# drivehersch.net
KiCad netlist of a schematic drawn in EAGLE
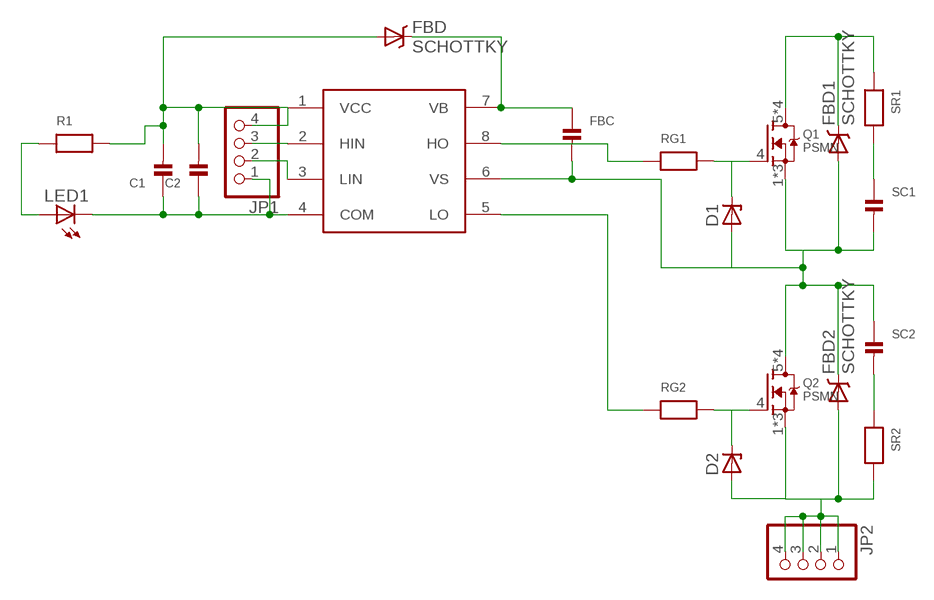
[diagram p0: schematic, sheet 1]

(export (version "E")
  (design (tool "Eeschema 10.0.6"))
  (components
    (comp (ref "C1")
      (value "CAP_CERAMIC1206")
      (footprint "eagle-import:1206")
      (libsource (lib "eagle-import") (part "CAP_CERAMIC1206"))
    )
    (comp (ref "C2")
      (value "CAP_CERAMIC1206")
      (footprint "eagle-import:1206")
      (libsource (lib "eagle-import") (part "CAP_CERAMIC1206"))
    )
    (comp (ref "D1")
      (value "ZENER-DIODESOT23")
      (footprint "eagle-import:SOT23")
      (libsource (lib "eagle-import") (part "ZENER-DIODESOT23"))
    )
    (comp (ref "D2")
      (value "ZENER-DIODESOT23")
      (footprint "eagle-import:SOT23")
      (libsource (lib "eagle-import") (part "ZENER-DIODESOT23"))
    )
    (comp (ref "FBC")
      (value "CAP_CERAMIC1206")
      (footprint "eagle-import:1206")
      (libsource (lib "eagle-import") (part "CAP_CERAMIC1206"))
    )
    (comp (ref "FBD")
      (value "SCHOTTKY")
      (footprint "eagle-import:SMA-DIODE")
      (libsource (lib "eagle-import") (part "SCHOTTKY"))
    )
    (comp (ref "FBD1")
      (value "SCHOTTKY")
      (footprint "eagle-import:SMA-DIODE")
      (libsource (lib "eagle-import") (part "SCHOTTKY"))
    )
    (comp (ref "FBD2")
      (value "SCHOTTKY")
      (footprint "eagle-import:SMA-DIODE")
      (libsource (lib "eagle-import") (part "SCHOTTKY"))
    )
    (comp (ref "JP1")
      (value "HEADER-1X4ROUND")
      (footprint "eagle-import:1X04_ROUND")
      (libsource (lib "eagle-import") (part "HEADER-1X4ROUND"))
    )
    (comp (ref "JP2")
      (value "HEADER-1X4ROUND")
      (footprint "eagle-import:1X04_ROUND")
      (libsource (lib "eagle-import") (part "HEADER-1X4ROUND"))
    )
    (comp (ref "LED1")
      (value "LEDCHIPLED_0603")
      (footprint "eagle-import:CHIPLED_0603")
      (libsource (lib "eagle-import") (part "LEDCHIPLED_0603"))
    )
    (comp (ref "Q1")
      (value "PSMN")
      (footprint "eagle-import:SO-08")
      (libsource (lib "eagle-import") (part "PSMN"))
    )
    (comp (ref "Q2")
      (value "PSMN")
      (footprint "eagle-import:SO-08")
      (libsource (lib "eagle-import") (part "PSMN"))
    )
    (comp (ref "R1")
      (value "RESISTOR0603")
      (footprint "eagle-import:0603")
      (libsource (lib "eagle-import") (part "RESISTOR0603"))
    )
    (comp (ref "RG1")
      (value "RESISTOR0603")
      (footprint "eagle-import:0603")
      (libsource (lib "eagle-import") (part "RESISTOR0603"))
    )
    (comp (ref "RG2")
      (value "RESISTOR0603")
      (footprint "eagle-import:0603")
      (libsource (lib "eagle-import") (part "RESISTOR0603"))
    )
    (comp (ref "SC1")
      (value "CAP_CERAMIC0603")
      (footprint "eagle-import:0603")
      (libsource (lib "eagle-import") (part "CAP_CERAMIC0603"))
    )
    (comp (ref "SC2")
      (value "CAP_CERAMIC0603")
      (footprint "eagle-import:0603")
      (libsource (lib "eagle-import") (part "CAP_CERAMIC0603"))
    )
    (comp (ref "SR1")
      (value "RESISTOR0603")
      (footprint "eagle-import:0603")
      (libsource (lib "eagle-import") (part "RESISTOR0603"))
    )
    (comp (ref "SR2")
      (value "RESISTOR0603")
      (footprint "eagle-import:0603")
      (libsource (lib "eagle-import") (part "RESISTOR0603"))
    )
    (comp (ref "U$1")
      (value "IRS218-67")
      (footprint "eagle-import:SO-08")
      (libsource (lib "eagle-import") (part "IRS218-67"))
    )
  )
  (nets
    (net (code "1") (name "/GND") (class "Default")
      (node (ref "C1") (pin "1") (pinfunction "P$1_1") (pintype "passive"))
      (node (ref "C2") (pin "1") (pinfunction "P$1_1") (pintype "passive"))
      (node (ref "D2") (pin "1") (pinfunction "A_1") (pintype "passive"))
      (node (ref "FBD2") (pin "A") (pinfunction "A_A") (pintype "passive"))
      (node (ref "JP1") (pin "1") (pinfunction "1_1") (pintype "passive"))
      (node (ref "JP2") (pin "1") (pinfunction "1_1") (pintype "passive"))
      (node (ref "JP2") (pin "2") (pinfunction "2_2") (pintype "passive"))
      (node (ref "JP2") (pin "3") (pinfunction "3_3") (pintype "passive"))
      (node (ref "JP2") (pin "4") (pinfunction "4_4") (pintype "passive"))
      (node (ref "LED1") (pin "C") (pinfunction "C_C") (pintype "passive"))
      (node (ref "Q2") (pin "1") (pinfunction "S_1") (pintype "bidirectional"))
      (node (ref "Q2") (pin "2") (pinfunction "S_2") (pintype "bidirectional"))
      (node (ref "Q2") (pin "3") (pinfunction "S_3") (pintype "bidirectional"))
      (node (ref "SR2") (pin "2") (pinfunction "2_2") (pintype "passive"))
      (node (ref "U$1") (pin "4") (pinfunction "COM_4") (pintype "bidirectional"))
    )
    (net (code "2") (name "Net-(C1-P$2)") (class "Default")
      (node (ref "C1") (pin "2") (pinfunction "P$2_2") (pintype "passive"))
      (node (ref "C2") (pin "2") (pinfunction "P$2_2") (pintype "passive"))
      (node (ref "FBD") (pin "A") (pinfunction "A_A") (pintype "passive"))
      (node (ref "JP1") (pin "4") (pinfunction "4_4") (pintype "passive"))
      (node (ref "R1") (pin "2") (pinfunction "2_2") (pintype "passive"))
      (node (ref "U$1") (pin "1") (pinfunction "VCC_1") (pintype "bidirectional"))
    )
    (net (code "3") (name "Net-(D1-A)") (class "Default")
      (node (ref "D1") (pin "1") (pinfunction "A_1") (pintype "passive"))
      (node (ref "FBC") (pin "2") (pinfunction "P$2_2") (pintype "passive"))
      (node (ref "FBD1") (pin "A") (pinfunction "A_A") (pintype "passive"))
      (node (ref "FBD2") (pin "C") (pinfunction "C_C") (pintype "passive"))
      (node (ref "Q1") (pin "1") (pinfunction "S_1") (pintype "bidirectional"))
      (node (ref "Q1") (pin "2") (pinfunction "S_2") (pintype "bidirectional"))
      (node (ref "Q1") (pin "3") (pinfunction "S_3") (pintype "bidirectional"))
      (node (ref "Q2") (pin "5") (pinfunction "D_5") (pintype "bidirectional"))
      (node (ref "Q2") (pin "6") (pinfunction "D_6") (pintype "bidirectional"))
      (node (ref "Q2") (pin "7") (pinfunction "D_7") (pintype "bidirectional"))
      (node (ref "Q2") (pin "8") (pinfunction "D_8") (pintype "bidirectional"))
      (node (ref "SC1") (pin "2") (pinfunction "P$2_2") (pintype "passive"))
      (node (ref "SC2") (pin "1") (pinfunction "P$1_1") (pintype "passive"))
      (node (ref "U$1") (pin "6") (pinfunction "VS_6") (pintype "bidirectional"))
    )
    (net (code "4") (name "Net-(D1-C)") (class "Default")
      (node (ref "D1") (pin "3") (pinfunction "C_3") (pintype "passive"))
      (node (ref "Q1") (pin "4") (pinfunction "G_4") (pintype "bidirectional"))
      (node (ref "RG1") (pin "2") (pinfunction "2_2") (pintype "passive"))
    )
    (net (code "5") (name "Net-(D2-C)") (class "Default")
      (node (ref "D2") (pin "3") (pinfunction "C_3") (pintype "passive"))
      (node (ref "Q2") (pin "4") (pinfunction "G_4") (pintype "bidirectional"))
      (node (ref "RG2") (pin "2") (pinfunction "2_2") (pintype "passive"))
    )
    (net (code "6") (name "Net-(FBC-P$1)") (class "Default")
      (node (ref "FBC") (pin "1") (pinfunction "P$1_1") (pintype "passive"))
      (node (ref "FBD") (pin "C") (pinfunction "C_C") (pintype "passive"))
      (node (ref "U$1") (pin "7") (pinfunction "VB_7") (pintype "bidirectional"))
    )
    (net (code "7") (name "Net-(FBD1-PadC)") (class "Default")
      (node (ref "FBD1") (pin "C") (pinfunction "C_C") (pintype "passive"))
      (node (ref "Q1") (pin "5") (pinfunction "D_5") (pintype "bidirectional"))
      (node (ref "Q1") (pin "6") (pinfunction "D_6") (pintype "bidirectional"))
      (node (ref "Q1") (pin "7") (pinfunction "D_7") (pintype "bidirectional"))
      (node (ref "Q1") (pin "8") (pinfunction "D_8") (pintype "bidirectional"))
      (node (ref "SR1") (pin "1") (pinfunction "1_1") (pintype "passive"))
    )
    (net (code "8") (name "Net-(LED1-PadA)") (class "Default")
      (node (ref "LED1") (pin "A") (pinfunction "A_A") (pintype "passive"))
      (node (ref "R1") (pin "1") (pinfunction "1_1") (pintype "passive"))
    )
    (net (code "9") (name "Net-(SC1-P$1)") (class "Default")
      (node (ref "SC1") (pin "1") (pinfunction "P$1_1") (pintype "passive"))
      (node (ref "SR1") (pin "2") (pinfunction "2_2") (pintype "passive"))
    )
    (net (code "10") (name "Net-(SC2-P$2)") (class "Default")
      (node (ref "SC2") (pin "2") (pinfunction "P$2_2") (pintype "passive"))
      (node (ref "SR2") (pin "1") (pinfunction "1_1") (pintype "passive"))
    )
    (net (code "11") (name "Net-(U$1-HIN)") (class "Default")
      (node (ref "JP1") (pin "3") (pinfunction "3_3") (pintype "passive"))
      (node (ref "U$1") (pin "2") (pinfunction "HIN_2") (pintype "bidirectional"))
    )
    (net (code "12") (name "Net-(U$1-HO)") (class "Default")
      (node (ref "RG1") (pin "1") (pinfunction "1_1") (pintype "passive"))
      (node (ref "U$1") (pin "8") (pinfunction "HO_8") (pintype "bidirectional"))
    )
    (net (code "13") (name "Net-(U$1-LIN)") (class "Default")
      (node (ref "JP1") (pin "2") (pinfunction "2_2") (pintype "passive"))
      (node (ref "U$1") (pin "3") (pinfunction "LIN_3") (pintype "bidirectional"))
    )
    (net (code "14") (name "Net-(U$1-LO)") (class "Default")
      (node (ref "RG2") (pin "1") (pinfunction "1_1") (pintype "passive"))
      (node (ref "U$1") (pin "5") (pinfunction "LO_5") (pintype "bidirectional"))
    )
  )
)
